# oe-headstage_BOB.net
KiCad netlist of a schematic drawn in EAGLE
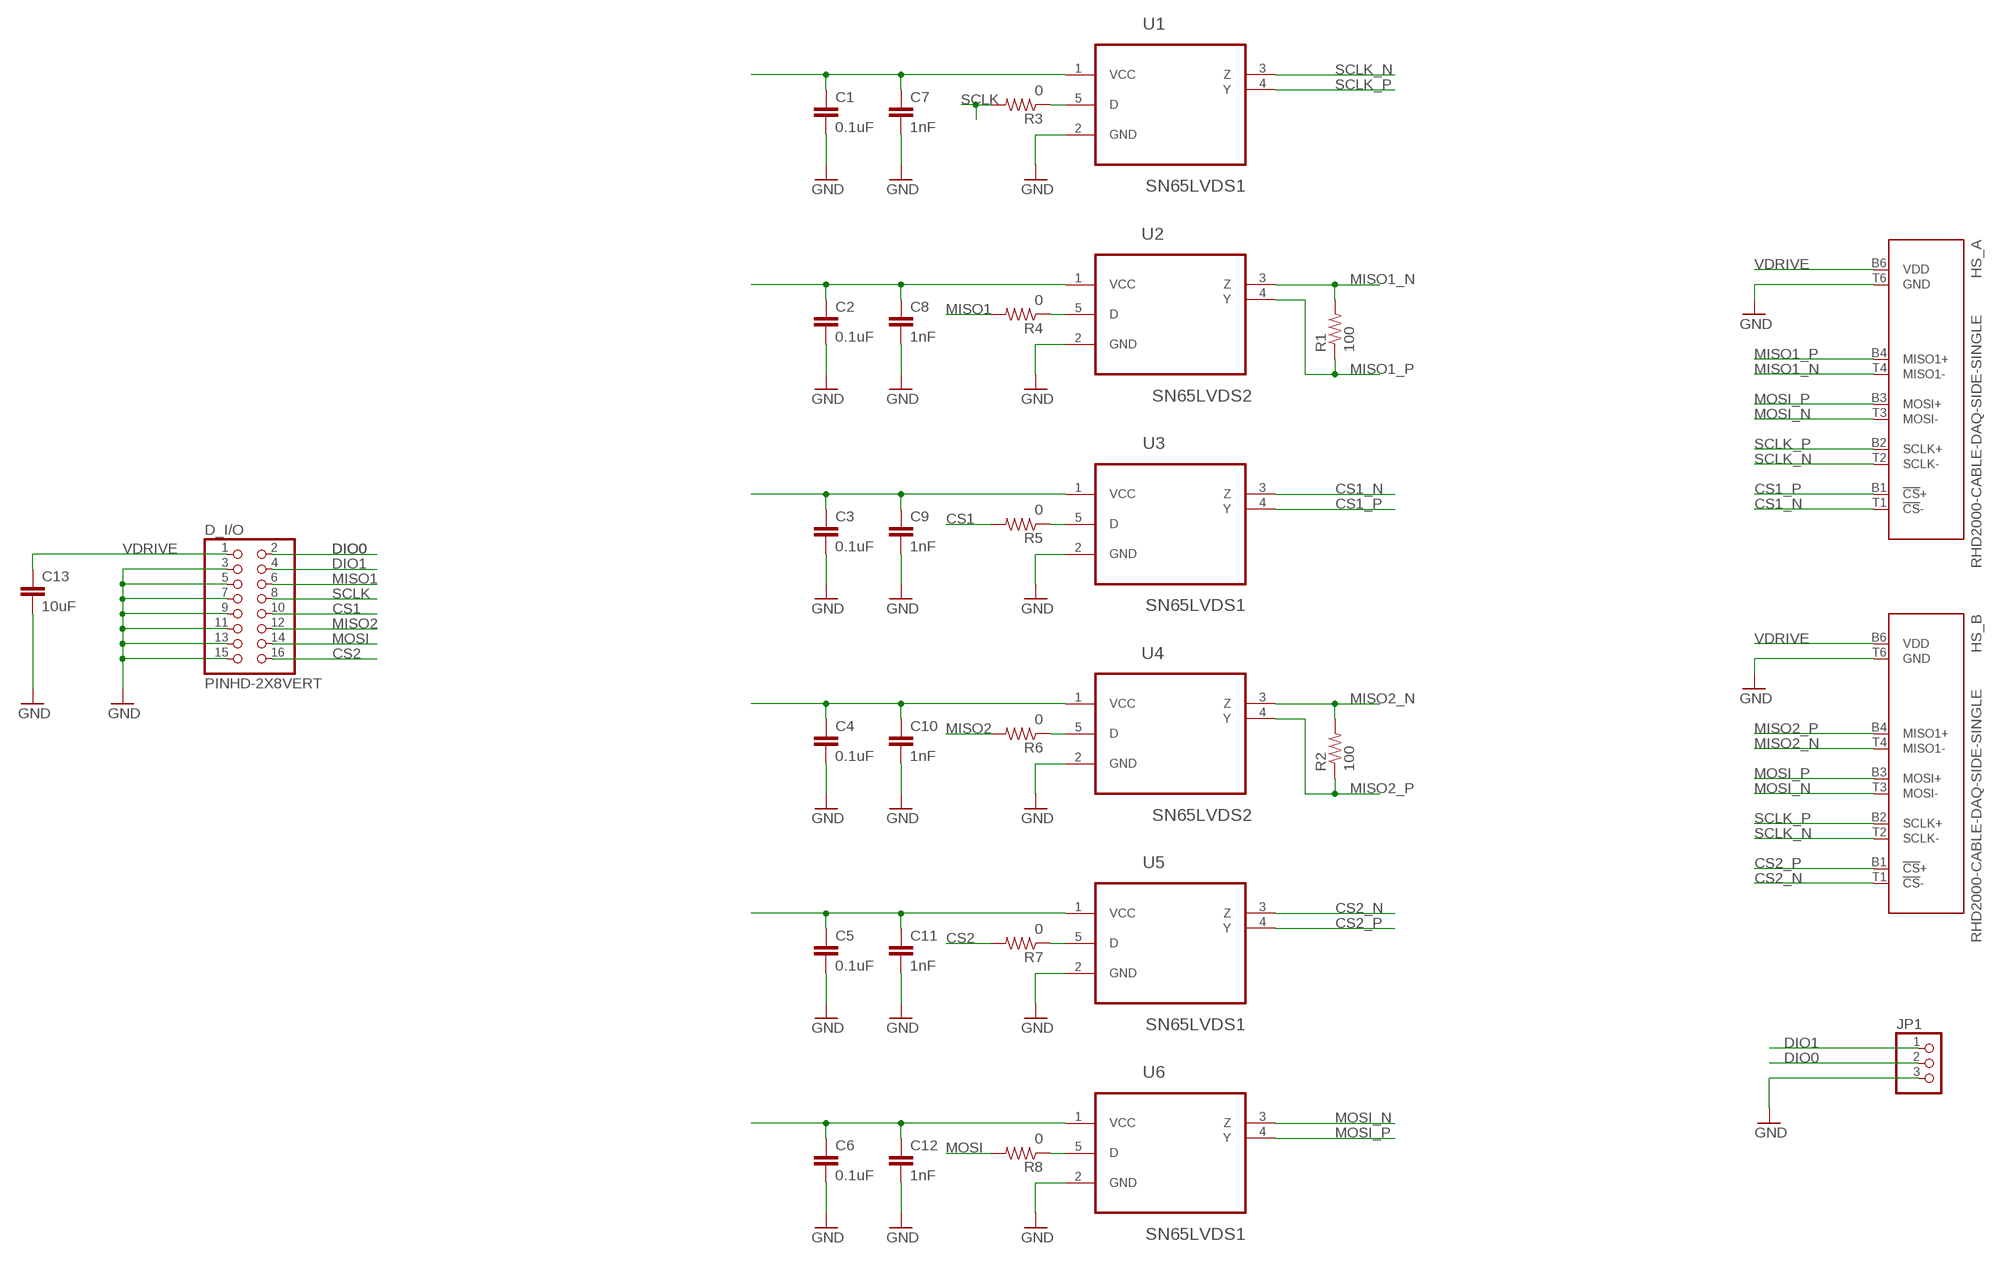
[diagram p0: schematic, sheet 1]

(export (version "E")
  (design (tool "Eeschema 10.0.6"))
  (components
    (comp (ref "C1")
      (value "0.1uF")
      (footprint "eagle-import:0603")
      (libsource (lib "eagle-import") (part "C_0603"))
    )
    (comp (ref "C2")
      (value "0.1uF")
      (footprint "eagle-import:0603")
      (libsource (lib "eagle-import") (part "C_0603"))
    )
    (comp (ref "C3")
      (value "0.1uF")
      (footprint "eagle-import:0603")
      (libsource (lib "eagle-import") (part "C_0603"))
    )
    (comp (ref "C4")
      (value "0.1uF")
      (footprint "eagle-import:0603")
      (libsource (lib "eagle-import") (part "C_0603"))
    )
    (comp (ref "C5")
      (value "0.1uF")
      (footprint "eagle-import:0603")
      (libsource (lib "eagle-import") (part "C_0603"))
    )
    (comp (ref "C6")
      (value "0.1uF")
      (footprint "eagle-import:0603")
      (libsource (lib "eagle-import") (part "C_0603"))
    )
    (comp (ref "C7")
      (value "1nF")
      (footprint "eagle-import:0603")
      (libsource (lib "eagle-import") (part "C_0603"))
    )
    (comp (ref "C8")
      (value "1nF")
      (footprint "eagle-import:0603")
      (libsource (lib "eagle-import") (part "C_0603"))
    )
    (comp (ref "C9")
      (value "1nF")
      (footprint "eagle-import:0603")
      (libsource (lib "eagle-import") (part "C_0603"))
    )
    (comp (ref "C10")
      (value "1nF")
      (footprint "eagle-import:0603")
      (libsource (lib "eagle-import") (part "C_0603"))
    )
    (comp (ref "C11")
      (value "1nF")
      (footprint "eagle-import:0603")
      (libsource (lib "eagle-import") (part "C_0603"))
    )
    (comp (ref "C12")
      (value "1nF")
      (footprint "eagle-import:0603")
      (libsource (lib "eagle-import") (part "C_0603"))
    )
    (comp (ref "C13")
      (value "10uF")
      (footprint "eagle-import:0805")
      (libsource (lib "eagle-import") (part "C_0805"))
    )
    (comp (ref "D_I/O")
      (value "PINHD-2X8VERT")
      (footprint "eagle-import:2X08")
      (libsource (lib "eagle-import") (part "PINHD-2X8VERT"))
    )
    (comp (ref "HS_A")
      (value "RHD2000-CABLE-DAQ-SIDE-SINGLE")
      (footprint "eagle-import:OMNETICS_PZN_12_AA-SINGLEBUS")
      (libsource (lib "eagle-import") (part "RHD2000-CABLE-DAQ-SIDE-SINGLE"))
    )
    (comp (ref "HS_B")
      (value "RHD2000-CABLE-DAQ-SIDE-SINGLE")
      (footprint "eagle-import:OMNETICS_PZN_12_AA-SINGLEBUS")
      (libsource (lib "eagle-import") (part "RHD2000-CABLE-DAQ-SIDE-SINGLE"))
    )
    (comp (ref "JP1")
      (value "PINHD-1X3")
      (footprint "eagle-import:1X03")
      (libsource (lib "eagle-import") (part "PINHD-1X3"))
    )
    (comp (ref "R1")
      (value "100")
      (footprint "eagle-import:0603")
      (libsource (lib "eagle-import") (part "R_0603"))
    )
    (comp (ref "R2")
      (value "100")
      (footprint "eagle-import:0603")
      (libsource (lib "eagle-import") (part "R_0603"))
    )
    (comp (ref "R3")
      (value "0")
      (footprint "eagle-import:0603")
      (libsource (lib "eagle-import") (part "R_0603"))
    )
    (comp (ref "R4")
      (value "0")
      (footprint "eagle-import:0603")
      (libsource (lib "eagle-import") (part "R_0603"))
    )
    (comp (ref "R5")
      (value "0")
      (footprint "eagle-import:0603")
      (libsource (lib "eagle-import") (part "R_0603"))
    )
    (comp (ref "R6")
      (value "0")
      (footprint "eagle-import:0603")
      (libsource (lib "eagle-import") (part "R_0603"))
    )
    (comp (ref "R7")
      (value "0")
      (footprint "eagle-import:0603")
      (libsource (lib "eagle-import") (part "R_0603"))
    )
    (comp (ref "R8")
      (value "0")
      (footprint "eagle-import:0603")
      (libsource (lib "eagle-import") (part "R_0603"))
    )
    (comp (ref "U1")
      (value "SN65LVDS1")
      (footprint "eagle-import:SOT95P280X145-5N")
      (fields (field (name "MPN") "SN65LVDS1DBVR"))
      (libsource (lib "eagle-import") (part "SN65LVDS1DBVR"))
    )
    (comp (ref "U2")
      (value "SN65LVDS2")
      (footprint "eagle-import:SOT95P280X145-5N")
      (fields (field (name "MPN") "SN65LVDS2DBVR"))
      (libsource (lib "eagle-import") (part "SN65LVDS2DBVR"))
    )
    (comp (ref "U3")
      (value "SN65LVDS1")
      (footprint "eagle-import:SOT95P280X145-5N")
      (fields (field (name "MPN") "SN65LVDS1DBVR"))
      (libsource (lib "eagle-import") (part "SN65LVDS1DBVR"))
    )
    (comp (ref "U4")
      (value "SN65LVDS2")
      (footprint "eagle-import:SOT95P280X145-5N")
      (fields (field (name "MPN") "SN65LVDS2DBVR"))
      (libsource (lib "eagle-import") (part "SN65LVDS2DBVR"))
    )
    (comp (ref "U5")
      (value "SN65LVDS1")
      (footprint "eagle-import:SOT95P280X145-5N")
      (fields (field (name "MPN") "SN65LVDS1DBVR"))
      (libsource (lib "eagle-import") (part "SN65LVDS1DBVR"))
    )
    (comp (ref "U6")
      (value "SN65LVDS1")
      (footprint "eagle-import:SOT95P280X145-5N")
      (fields (field (name "MPN") "SN65LVDS1DBVR"))
      (libsource (lib "eagle-import") (part "SN65LVDS1DBVR"))
    )
  )
  (nets
    (net (code "1") (name "/CS1") (class "Default")
      (node (ref "D_I/O") (pin "10") (pinfunction "10_10") (pintype "passive"))
      (node (ref "R5") (pin "2") (pinfunction "2_2") (pintype "passive"))
    )
    (net (code "2") (name "/CS1_N") (class "Default")
      (node (ref "HS_A") (pin "T1") (pinfunction "~{CS}-_T1") (pintype "bidirectional"))
      (node (ref "U3") (pin "3") (pinfunction "Z_3") (pintype "output"))
    )
    (net (code "3") (name "/CS1_P") (class "Default")
      (node (ref "HS_A") (pin "B1") (pinfunction "~{CS}+_B1") (pintype "bidirectional"))
      (node (ref "U3") (pin "4") (pinfunction "Y_4") (pintype "output"))
    )
    (net (code "4") (name "/CS2") (class "Default")
      (node (ref "D_I/O") (pin "16") (pinfunction "16_16") (pintype "passive"))
      (node (ref "R7") (pin "2") (pinfunction "2_2") (pintype "passive"))
    )
    (net (code "5") (name "/CS2_N") (class "Default")
      (node (ref "HS_B") (pin "T1") (pinfunction "~{CS}-_T1") (pintype "bidirectional"))
      (node (ref "U5") (pin "3") (pinfunction "Z_3") (pintype "output"))
    )
    (net (code "6") (name "/CS2_P") (class "Default")
      (node (ref "HS_B") (pin "B1") (pinfunction "~{CS}+_B1") (pintype "bidirectional"))
      (node (ref "U5") (pin "4") (pinfunction "Y_4") (pintype "output"))
    )
    (net (code "7") (name "/DIO0") (class "Default")
      (node (ref "D_I/O") (pin "2") (pinfunction "2_2") (pintype "passive"))
      (node (ref "JP1") (pin "2") (pinfunction "2_2") (pintype "passive"))
    )
    (net (code "8") (name "/DIO1") (class "Default")
      (node (ref "D_I/O") (pin "4") (pinfunction "4_4") (pintype "passive"))
      (node (ref "JP1") (pin "1") (pinfunction "1_1") (pintype "passive"))
    )
    (net (code "9") (name "/MISO1") (class "Default")
      (node (ref "D_I/O") (pin "6") (pinfunction "6_6") (pintype "passive"))
      (node (ref "R4") (pin "2") (pinfunction "2_2") (pintype "passive"))
    )
    (net (code "10") (name "/MISO1_N") (class "Default")
      (node (ref "HS_A") (pin "T4") (pinfunction "MISO1-_T4") (pintype "bidirectional"))
      (node (ref "R1") (pin "2") (pinfunction "2_2") (pintype "passive"))
      (node (ref "U2") (pin "3") (pinfunction "Z_3") (pintype "output"))
    )
    (net (code "11") (name "/MISO1_P") (class "Default")
      (node (ref "HS_A") (pin "B4") (pinfunction "MISO1+_B4") (pintype "bidirectional"))
      (node (ref "R1") (pin "1") (pinfunction "1_1") (pintype "passive"))
      (node (ref "U2") (pin "4") (pinfunction "Y_4") (pintype "output"))
    )
    (net (code "12") (name "/MISO2") (class "Default")
      (node (ref "D_I/O") (pin "12") (pinfunction "12_12") (pintype "passive"))
      (node (ref "R6") (pin "2") (pinfunction "2_2") (pintype "passive"))
    )
    (net (code "13") (name "/MISO2_N") (class "Default")
      (node (ref "HS_B") (pin "T4") (pinfunction "MISO1-_T4") (pintype "bidirectional"))
      (node (ref "R2") (pin "2") (pinfunction "2_2") (pintype "passive"))
      (node (ref "U4") (pin "3") (pinfunction "Z_3") (pintype "output"))
    )
    (net (code "14") (name "/MISO2_P") (class "Default")
      (node (ref "HS_B") (pin "B4") (pinfunction "MISO1+_B4") (pintype "bidirectional"))
      (node (ref "R2") (pin "1") (pinfunction "1_1") (pintype "passive"))
      (node (ref "U4") (pin "4") (pinfunction "Y_4") (pintype "output"))
    )
    (net (code "15") (name "/MOSI") (class "Default")
      (node (ref "D_I/O") (pin "14") (pinfunction "14_14") (pintype "passive"))
      (node (ref "R8") (pin "2") (pinfunction "2_2") (pintype "passive"))
    )
    (net (code "16") (name "/MOSI_N") (class "Default")
      (node (ref "HS_A") (pin "T3") (pinfunction "MOSI-_T3") (pintype "bidirectional"))
      (node (ref "HS_B") (pin "T3") (pinfunction "MOSI-_T3") (pintype "bidirectional"))
      (node (ref "U6") (pin "3") (pinfunction "Z_3") (pintype "output"))
    )
    (net (code "17") (name "/MOSI_P") (class "Default")
      (node (ref "HS_A") (pin "B3") (pinfunction "MOSI+_B3") (pintype "bidirectional"))
      (node (ref "HS_B") (pin "B3") (pinfunction "MOSI+_B3") (pintype "bidirectional"))
      (node (ref "U6") (pin "4") (pinfunction "Y_4") (pintype "output"))
    )
    (net (code "18") (name "/SCLK") (class "Default")
      (node (ref "D_I/O") (pin "8") (pinfunction "8_8") (pintype "passive"))
      (node (ref "R3") (pin "2") (pinfunction "2_2") (pintype "passive"))
    )
    (net (code "19") (name "/SCLK_N") (class "Default")
      (node (ref "HS_A") (pin "T2") (pinfunction "SCLK-_T2") (pintype "bidirectional"))
      (node (ref "HS_B") (pin "T2") (pinfunction "SCLK-_T2") (pintype "bidirectional"))
      (node (ref "U1") (pin "3") (pinfunction "Z_3") (pintype "output"))
    )
    (net (code "20") (name "/SCLK_P") (class "Default")
      (node (ref "HS_A") (pin "B2") (pinfunction "SCLK+_B2") (pintype "bidirectional"))
      (node (ref "HS_B") (pin "B2") (pinfunction "SCLK+_B2") (pintype "bidirectional"))
      (node (ref "U1") (pin "4") (pinfunction "Y_4") (pintype "output"))
    )
    (net (code "21") (name "/VDRIVE") (class "Default")
      (node (ref "C1") (pin "1") (pinfunction "1_1") (pintype "passive"))
      (node (ref "C10") (pin "1") (pinfunction "1_1") (pintype "passive"))
      (node (ref "C11") (pin "1") (pinfunction "1_1") (pintype "passive"))
      (node (ref "C12") (pin "1") (pinfunction "1_1") (pintype "passive"))
      (node (ref "C13") (pin "1") (pinfunction "1_1") (pintype "passive"))
      (node (ref "C2") (pin "1") (pinfunction "1_1") (pintype "passive"))
      (node (ref "C3") (pin "1") (pinfunction "1_1") (pintype "passive"))
      (node (ref "C4") (pin "1") (pinfunction "1_1") (pintype "passive"))
      (node (ref "C5") (pin "1") (pinfunction "1_1") (pintype "passive"))
      (node (ref "C6") (pin "1") (pinfunction "1_1") (pintype "passive"))
      (node (ref "C7") (pin "1") (pinfunction "1_1") (pintype "passive"))
      (node (ref "C8") (pin "1") (pinfunction "1_1") (pintype "passive"))
      (node (ref "C9") (pin "1") (pinfunction "1_1") (pintype "passive"))
      (node (ref "D_I/O") (pin "1") (pinfunction "1_1") (pintype "passive"))
      (node (ref "HS_A") (pin "B6") (pinfunction "VDD_B6") (pintype "bidirectional"))
      (node (ref "HS_B") (pin "B6") (pinfunction "VDD_B6") (pintype "bidirectional"))
      (node (ref "U1") (pin "1") (pinfunction "VCC_1") (pintype "power_in"))
      (node (ref "U2") (pin "1") (pinfunction "VCC_1") (pintype "power_in"))
      (node (ref "U3") (pin "1") (pinfunction "VCC_1") (pintype "power_in"))
      (node (ref "U4") (pin "1") (pinfunction "VCC_1") (pintype "power_in"))
      (node (ref "U5") (pin "1") (pinfunction "VCC_1") (pintype "power_in"))
      (node (ref "U6") (pin "1") (pinfunction "VCC_1") (pintype "power_in"))
    )
    (net (code "22") (name "GND") (class "Default")
      (node (ref "C1") (pin "2") (pinfunction "2_2") (pintype "passive"))
      (node (ref "C10") (pin "2") (pinfunction "2_2") (pintype "passive"))
      (node (ref "C11") (pin "2") (pinfunction "2_2") (pintype "passive"))
      (node (ref "C12") (pin "2") (pinfunction "2_2") (pintype "passive"))
      (node (ref "C13") (pin "2") (pinfunction "2_2") (pintype "passive"))
      (node (ref "C2") (pin "2") (pinfunction "2_2") (pintype "passive"))
      (node (ref "C3") (pin "2") (pinfunction "2_2") (pintype "passive"))
      (node (ref "C4") (pin "2") (pinfunction "2_2") (pintype "passive"))
      (node (ref "C5") (pin "2") (pinfunction "2_2") (pintype "passive"))
      (node (ref "C6") (pin "2") (pinfunction "2_2") (pintype "passive"))
      (node (ref "C7") (pin "2") (pinfunction "2_2") (pintype "passive"))
      (node (ref "C8") (pin "2") (pinfunction "2_2") (pintype "passive"))
      (node (ref "C9") (pin "2") (pinfunction "2_2") (pintype "passive"))
      (node (ref "D_I/O") (pin "11") (pinfunction "11_11") (pintype "passive"))
      (node (ref "D_I/O") (pin "13") (pinfunction "13_13") (pintype "passive"))
      (node (ref "D_I/O") (pin "15") (pinfunction "15_15") (pintype "passive"))
      (node (ref "D_I/O") (pin "3") (pinfunction "3_3") (pintype "passive"))
      (node (ref "D_I/O") (pin "5") (pinfunction "5_5") (pintype "passive"))
      (node (ref "D_I/O") (pin "7") (pinfunction "7_7") (pintype "passive"))
      (node (ref "D_I/O") (pin "9") (pinfunction "9_9") (pintype "passive"))
      (node (ref "HS_A") (pin "T6") (pinfunction "GND_T6") (pintype "power_in"))
      (node (ref "HS_B") (pin "T6") (pinfunction "GND_T6") (pintype "power_in"))
      (node (ref "JP1") (pin "3") (pinfunction "3_3") (pintype "passive"))
      (node (ref "U1") (pin "2") (pinfunction "GND_2") (pintype "passive"))
      (node (ref "U2") (pin "2") (pinfunction "GND_2") (pintype "passive"))
      (node (ref "U3") (pin "2") (pinfunction "GND_2") (pintype "passive"))
      (node (ref "U4") (pin "2") (pinfunction "GND_2") (pintype "passive"))
      (node (ref "U5") (pin "2") (pinfunction "GND_2") (pintype "passive"))
      (node (ref "U6") (pin "2") (pinfunction "GND_2") (pintype "passive"))
    )
    (net (code "23") (name "Net-(U1-D)") (class "Default")
      (node (ref "R3") (pin "1") (pinfunction "1_1") (pintype "passive"))
      (node (ref "U1") (pin "5") (pinfunction "D_5") (pintype "input"))
    )
    (net (code "24") (name "Net-(U2-D)") (class "Default")
      (node (ref "R4") (pin "1") (pinfunction "1_1") (pintype "passive"))
      (node (ref "U2") (pin "5") (pinfunction "D_5") (pintype "input"))
    )
    (net (code "25") (name "Net-(U3-D)") (class "Default")
      (node (ref "R5") (pin "1") (pinfunction "1_1") (pintype "passive"))
      (node (ref "U3") (pin "5") (pinfunction "D_5") (pintype "input"))
    )
    (net (code "26") (name "Net-(U4-D)") (class "Default")
      (node (ref "R6") (pin "1") (pinfunction "1_1") (pintype "passive"))
      (node (ref "U4") (pin "5") (pinfunction "D_5") (pintype "input"))
    )
    (net (code "27") (name "Net-(U5-D)") (class "Default")
      (node (ref "R7") (pin "1") (pinfunction "1_1") (pintype "passive"))
      (node (ref "U5") (pin "5") (pinfunction "D_5") (pintype "input"))
    )
    (net (code "28") (name "Net-(U6-D)") (class "Default")
      (node (ref "R8") (pin "1") (pinfunction "1_1") (pintype "passive"))
      (node (ref "U6") (pin "5") (pinfunction "D_5") (pintype "input"))
    )
  )
)
